# Main_board.net
KiCad netlist of a schematic drawn in EAGLE
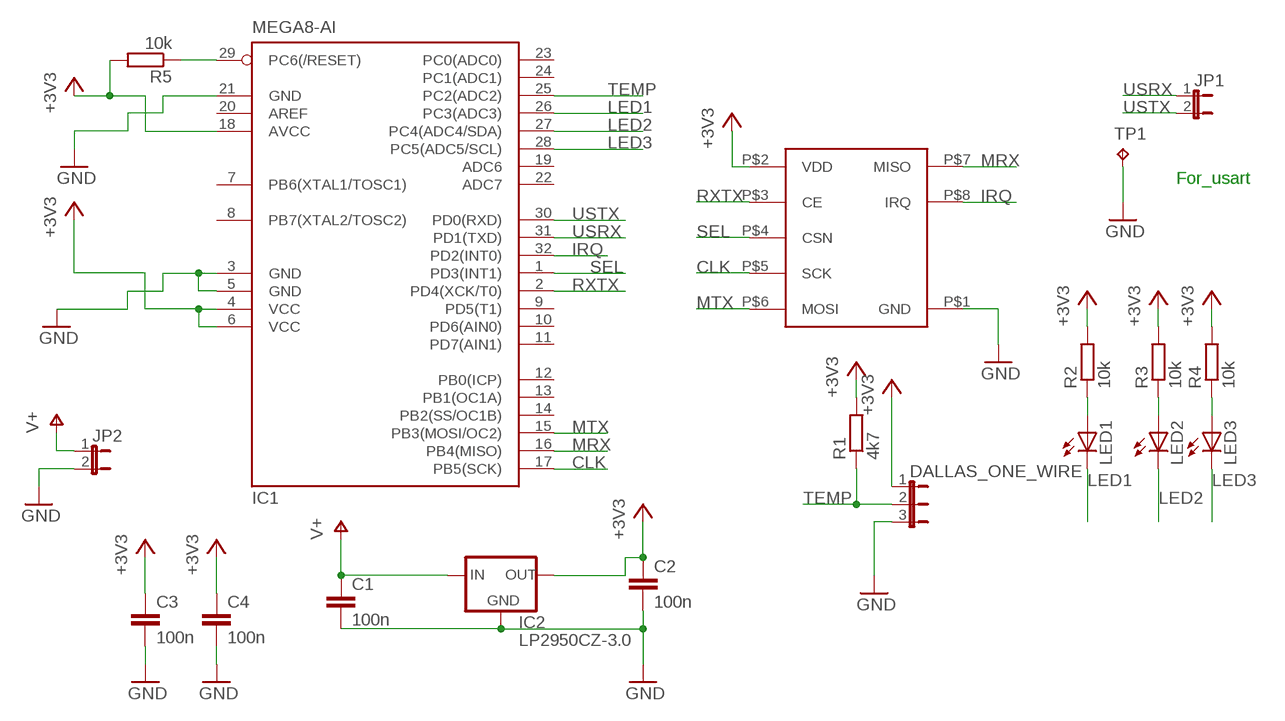
[diagram p0: schematic, sheet 1]

(export (version "E")
  (design (tool "Eeschema 10.0.6"))
  (components
    (comp (ref "C1")
      (value "100n")
      (footprint "eagle-import:C1206")
      (libsource (lib "eagle-import") (part "C-EUC1206"))
    )
    (comp (ref "C2")
      (value "100n")
      (footprint "eagle-import:C1206")
      (libsource (lib "eagle-import") (part "C-EUC1206"))
    )
    (comp (ref "C3")
      (value "100n")
      (footprint "eagle-import:C1206")
      (libsource (lib "eagle-import") (part "C-EUC1206"))
    )
    (comp (ref "C4")
      (value "100n")
      (footprint "eagle-import:C1206")
      (libsource (lib "eagle-import") (part "C-EUC1206"))
    )
    (comp (ref "DALLAS_ONE_WIRE")
      (value "JP2E")
      (footprint "eagle-import:JP2")
      (libsource (lib "eagle-import") (part "JP2E"))
    )
    (comp (ref "IC1")
      (value "MEGA8-AI")
      (footprint "eagle-import:TQFP32-08")
      (fields (field (name "MPN") "ATMEGA8-16AU"))
      (libsource (lib "eagle-import") (part "MEGA8-AI"))
    )
    (comp (ref "IC2")
      (value "LP2950CZ-3.0")
      (footprint "eagle-import:TO92")
      (libsource (lib "eagle-import") (part "LP2950?CZ-3.0"))
    )
    (comp (ref "JP1")
      (value "JP1E")
      (footprint "eagle-import:JP1")
      (libsource (lib "eagle-import") (part "JP1E"))
    )
    (comp (ref "JP2")
      (value "JP1E")
      (footprint "eagle-import:JP1")
      (libsource (lib "eagle-import") (part "JP1E"))
    )
    (comp (ref "LED1")
      (value "LEDSMT1206")
      (footprint "eagle-import:1206")
      (libsource (lib "eagle-import") (part "LEDSMT1206"))
    )
    (comp (ref "LED2")
      (value "LEDSMT1206")
      (footprint "eagle-import:1206")
      (libsource (lib "eagle-import") (part "LEDSMT1206"))
    )
    (comp (ref "LED3")
      (value "LEDSMT1206")
      (footprint "eagle-import:1206")
      (libsource (lib "eagle-import") (part "LEDSMT1206"))
    )
    (comp (ref "R1")
      (value "4k7")
      (footprint "eagle-import:M1206")
      (libsource (lib "eagle-import") (part "R-EU_M1206"))
    )
    (comp (ref "R2")
      (value "10k")
      (footprint "eagle-import:M1206")
      (libsource (lib "eagle-import") (part "R-EU_M1206"))
    )
    (comp (ref "R3")
      (value "10k")
      (footprint "eagle-import:M1206")
      (libsource (lib "eagle-import") (part "R-EU_M1206"))
    )
    (comp (ref "R4")
      (value "10k")
      (footprint "eagle-import:M1206")
      (libsource (lib "eagle-import") (part "R-EU_M1206"))
    )
    (comp (ref "R5")
      (value "10k")
      (footprint "eagle-import:M1206")
      (libsource (lib "eagle-import") (part "R-EU_M1206"))
    )
    (comp (ref "TP1")
      (value "TPB2,54")
      (footprint "eagle-import:B2,54")
      (libsource (lib "eagle-import") (part "TPB2,54"))
    )
    (comp (ref "U$1")
      (value "RFM70D")
      (footprint "eagle-import:RFM70D")
      (libsource (lib "eagle-import") (part "RFM70D"))
    )
  )
  (nets
    (net (code "1") (name "+3V3") (class "Default")
      (node (ref "C2") (pin "1") (pinfunction "1_1") (pintype "passive"))
      (node (ref "C3") (pin "1") (pinfunction "1_1") (pintype "passive"))
      (node (ref "C4") (pin "1") (pinfunction "1_1") (pintype "passive"))
      (node (ref "DALLAS_ONE_WIRE") (pin "1") (pinfunction "1_1") (pintype "passive"))
      (node (ref "IC1") (pin "18") (pinfunction "AVCC_18") (pintype "power_in"))
      (node (ref "IC1") (pin "4") (pinfunction "VCC_4") (pintype "power_in"))
      (node (ref "IC1") (pin "6") (pinfunction "VCC_6") (pintype "power_in"))
      (node (ref "IC2") (pin "1") (pinfunction "OUT_1") (pintype "passive"))
      (node (ref "R1") (pin "2") (pinfunction "2_2") (pintype "passive"))
      (node (ref "R2") (pin "2") (pinfunction "2_2") (pintype "passive"))
      (node (ref "R3") (pin "2") (pinfunction "2_2") (pintype "passive"))
      (node (ref "R4") (pin "2") (pinfunction "2_2") (pintype "passive"))
      (node (ref "R5") (pin "2") (pinfunction "2_2") (pintype "passive"))
      (node (ref "U$1") (pin "P$2") (pinfunction "VDD_P$2") (pintype "power_in"))
    )
    (net (code "2") (name "/CLK") (class "Default")
      (node (ref "IC1") (pin "17") (pinfunction "PB5(SCK)_17") (pintype "bidirectional"))
      (node (ref "U$1") (pin "P$5") (pinfunction "SCK_P$5") (pintype "input"))
    )
    (net (code "3") (name "/IRQ") (class "Default")
      (node (ref "IC1") (pin "32") (pinfunction "PD2(INT0)_32") (pintype "bidirectional"))
      (node (ref "U$1") (pin "P$8") (pinfunction "IRQ_P$8") (pintype "output"))
    )
    (net (code "4") (name "/LED1") (class "Default")
      (node (ref "IC1") (pin "26") (pinfunction "PC3(ADC3)_26") (pintype "bidirectional"))
      (node (ref "LED1") (pin "C") (pinfunction "C_C") (pintype "passive"))
    )
    (net (code "5") (name "/LED2") (class "Default")
      (node (ref "IC1") (pin "27") (pinfunction "PC4(ADC4/SDA)_27") (pintype "bidirectional"))
      (node (ref "LED2") (pin "C") (pinfunction "C_C") (pintype "passive"))
    )
    (net (code "6") (name "/LED3") (class "Default")
      (node (ref "IC1") (pin "28") (pinfunction "PC5(ADC5/SCL)_28") (pintype "bidirectional"))
      (node (ref "LED3") (pin "C") (pinfunction "C_C") (pintype "passive"))
    )
    (net (code "7") (name "/MRX") (class "Default")
      (node (ref "IC1") (pin "16") (pinfunction "PB4(MISO)_16") (pintype "bidirectional"))
      (node (ref "U$1") (pin "P$7") (pinfunction "MISO_P$7") (pintype "output"))
    )
    (net (code "8") (name "/MTX") (class "Default")
      (node (ref "IC1") (pin "15") (pinfunction "PB3(MOSI/OC2)_15") (pintype "bidirectional"))
      (node (ref "U$1") (pin "P$6") (pinfunction "MOSI_P$6") (pintype "input"))
    )
    (net (code "9") (name "/RXTX") (class "Default")
      (node (ref "IC1") (pin "2") (pinfunction "PD4(XCK/T0)_2") (pintype "bidirectional"))
      (node (ref "U$1") (pin "P$3") (pinfunction "CE_P$3") (pintype "input"))
    )
    (net (code "10") (name "/SEL") (class "Default")
      (node (ref "IC1") (pin "1") (pinfunction "PD3(INT1)_1") (pintype "bidirectional"))
      (node (ref "U$1") (pin "P$4") (pinfunction "CSN_P$4") (pintype "input"))
    )
    (net (code "11") (name "/TEMP") (class "Default")
      (node (ref "DALLAS_ONE_WIRE") (pin "2") (pinfunction "2_2") (pintype "passive"))
      (node (ref "IC1") (pin "25") (pinfunction "PC2(ADC2)_25") (pintype "bidirectional"))
      (node (ref "R1") (pin "1") (pinfunction "1_1") (pintype "passive"))
    )
    (net (code "12") (name "/USRX") (class "Default")
      (node (ref "IC1") (pin "31") (pinfunction "PD1(TXD)_31") (pintype "bidirectional"))
      (node (ref "JP1") (pin "1") (pinfunction "1_1") (pintype "passive"))
    )
    (net (code "13") (name "/USTX") (class "Default")
      (node (ref "IC1") (pin "30") (pinfunction "PD0(RXD)_30") (pintype "bidirectional"))
      (node (ref "JP1") (pin "2") (pinfunction "2_2") (pintype "passive"))
    )
    (net (code "14") (name "GND") (class "Default")
      (node (ref "C1") (pin "2") (pinfunction "2_2") (pintype "passive"))
      (node (ref "C2") (pin "2") (pinfunction "2_2") (pintype "passive"))
      (node (ref "C3") (pin "2") (pinfunction "2_2") (pintype "passive"))
      (node (ref "C4") (pin "2") (pinfunction "2_2") (pintype "passive"))
      (node (ref "DALLAS_ONE_WIRE") (pin "3") (pinfunction "3_3") (pintype "passive"))
      (node (ref "IC1") (pin "21") (pinfunction "GND_21") (pintype "power_in"))
      (node (ref "IC1") (pin "3") (pinfunction "GND_3") (pintype "power_in"))
      (node (ref "IC1") (pin "5") (pinfunction "GND_5") (pintype "power_in"))
      (node (ref "IC2") (pin "2") (pinfunction "GND_2") (pintype "input"))
      (node (ref "JP2") (pin "2") (pinfunction "2_2") (pintype "passive"))
      (node (ref "TP1") (pin "TP") (pinfunction "TP_TP") (pintype "input"))
      (node (ref "U$1") (pin "P$1") (pinfunction "GND_P$1") (pintype "power_in"))
    )
    (net (code "15") (name "Net-(IC1-PC6({slash}RESET))") (class "Default")
      (node (ref "IC1") (pin "29") (pinfunction "PC6(/RESET)_29") (pintype "bidirectional"))
      (node (ref "R5") (pin "1") (pinfunction "1_1") (pintype "passive"))
    )
    (net (code "16") (name "Net-(LED1-PadA)") (class "Default")
      (node (ref "LED1") (pin "A") (pinfunction "A_A") (pintype "passive"))
      (node (ref "R2") (pin "1") (pinfunction "1_1") (pintype "passive"))
    )
    (net (code "17") (name "Net-(LED2-PadA)") (class "Default")
      (node (ref "LED2") (pin "A") (pinfunction "A_A") (pintype "passive"))
      (node (ref "R3") (pin "1") (pinfunction "1_1") (pintype "passive"))
    )
    (net (code "18") (name "Net-(LED3-PadA)") (class "Default")
      (node (ref "LED3") (pin "A") (pinfunction "A_A") (pintype "passive"))
      (node (ref "R4") (pin "1") (pinfunction "1_1") (pintype "passive"))
    )
    (net (code "19") (name "V+") (class "Default")
      (node (ref "C1") (pin "1") (pinfunction "1_1") (pintype "passive"))
      (node (ref "IC2") (pin "3") (pinfunction "IN_3") (pintype "input"))
      (node (ref "JP2") (pin "1") (pinfunction "1_1") (pintype "passive"))
    )
    (net (code "20") (name "unconnected-(IC1-ADC6-Pad19)") (class "Default")
      (node (ref "IC1") (pin "19") (pinfunction "ADC6_19") (pintype "bidirectional"))
    )
    (net (code "21") (name "unconnected-(IC1-ADC7-Pad22)") (class "Default")
      (node (ref "IC1") (pin "22") (pinfunction "ADC7_22") (pintype "bidirectional"))
    )
    (net (code "22") (name "unconnected-(IC1-AREF-Pad20)") (class "Default")
      (node (ref "IC1") (pin "20") (pinfunction "AREF_20") (pintype "passive"))
    )
    (net (code "23") (name "unconnected-(IC1-PB0(ICP)-Pad12)") (class "Default")
      (node (ref "IC1") (pin "12") (pinfunction "PB0(ICP)_12") (pintype "bidirectional"))
    )
    (net (code "24") (name "unconnected-(IC1-PB1(OC1A)-Pad13)") (class "Default")
      (node (ref "IC1") (pin "13") (pinfunction "PB1(OC1A)_13") (pintype "bidirectional"))
    )
    (net (code "25") (name "unconnected-(IC1-PB2(SS{slash}OC1B)-Pad14)") (class "Default")
      (node (ref "IC1") (pin "14") (pinfunction "PB2(SS/OC1B)_14") (pintype "bidirectional"))
    )
    (net (code "26") (name "unconnected-(IC1-PB6(XTAL1{slash}TOSC1)-Pad7)") (class "Default")
      (node (ref "IC1") (pin "7") (pinfunction "PB6(XTAL1/TOSC1)_7") (pintype "bidirectional"))
    )
    (net (code "27") (name "unconnected-(IC1-PB7(XTAL2{slash}TOSC2)-Pad8)") (class "Default")
      (node (ref "IC1") (pin "8") (pinfunction "PB7(XTAL2/TOSC2)_8") (pintype "bidirectional"))
    )
    (net (code "28") (name "unconnected-(IC1-PC0(ADC0)-Pad23)") (class "Default")
      (node (ref "IC1") (pin "23") (pinfunction "PC0(ADC0)_23") (pintype "bidirectional"))
    )
    (net (code "29") (name "unconnected-(IC1-PC1(ADC1)-Pad24)") (class "Default")
      (node (ref "IC1") (pin "24") (pinfunction "PC1(ADC1)_24") (pintype "bidirectional"))
    )
    (net (code "30") (name "unconnected-(IC1-PD5(T1)-Pad9)") (class "Default")
      (node (ref "IC1") (pin "9") (pinfunction "PD5(T1)_9") (pintype "bidirectional"))
    )
    (net (code "31") (name "unconnected-(IC1-PD6(AIN0)-Pad10)") (class "Default")
      (node (ref "IC1") (pin "10") (pinfunction "PD6(AIN0)_10") (pintype "bidirectional"))
    )
    (net (code "32") (name "unconnected-(IC1-PD7(AIN1)-Pad11)") (class "Default")
      (node (ref "IC1") (pin "11") (pinfunction "PD7(AIN1)_11") (pintype "bidirectional"))
    )
  )
)
